# BMS_Carrier_-_AFE_Interface.net
KiCad netlist of a schematic drawn in Altium Designer
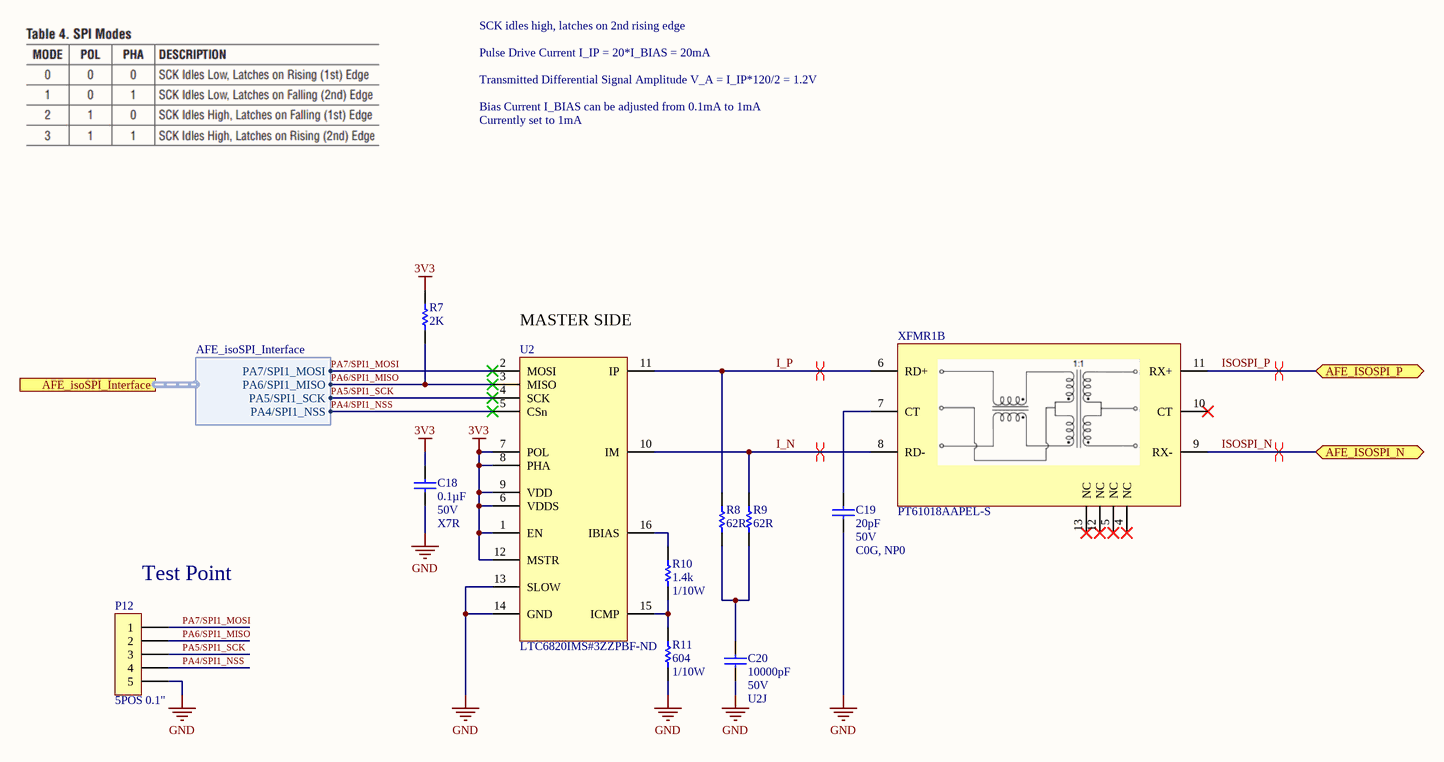
[diagram p0: BMS Carrier - AFE Interface.SchDoc]

(export (version "E")
  (design (tool "Eeschema 10.0.6"))
  (components
    (comp (ref "C18")
      (value "CAP CER 0.1UF 50V 10% X7R 0603")
      (footprint "CAP, 0603")
      (description "0.10µF ±10% 50V Ceramic Capacitor X7R 0603 (1608 Metric)")
      (fields
        (field (name "TOLERANCE") "±10%")
        (field (name "CAPACITANCE") "0.1µF")
        (field (name "VOLTAGE") "50V")
        (field (name "TEMPERATURE COEFFICIENT") "X7R")
      )
      (libsource (lib "Schematic Diagrams") (part "CAP CER 0.1UF 50V 10% X7R 0603"))
    )
    (comp (ref "C19")
      (value "CAP CER 20PF 50V ±5% C0G/NP0 0603")
      (footprint "CAP, 0603")
      (description "20pF ±5% 50V Ceramic Capacitor C0G, NP0 0603 (1608 Metric)")
      (fields
        (field (name "TOLERANCE") "±5%")
        (field (name "CAPACITANCE") "20pF")
        (field (name "VOLTAGE") "50V")
        (field (name "TEMPERATURE COEFFICIENT") "C0G, NP0")
      )
      (libsource (lib "Schematic Diagrams") (part "CAP CER 20PF 50V ±5% C0G/NP0 0603"))
    )
    (comp (ref "C20")
      (value "CAP CER 10nF 50V 5% X7R 0603")
      (footprint "CAP, 0603")
      (description "10000pF ±5% 50V Ceramic Capacitor U2J 0603 (1608 Metric)")
      (fields
        (field (name "TOLERANCE") "±5%")
        (field (name "CAPACITANCE") "10000pF")
        (field (name "VOLTAGE") "50V")
        (field (name "TEMPERATURE COEFFICIENT") "U2J")
      )
      (libsource (lib "Schematic Diagrams") (part "CAP CER 10nF 50V 5% X7R 0603"))
    )
    (comp (ref "P12")
      (value "5POS 0.1\"")
      (footprint "CONN, 5POS HEADR 0.1\"")
      (libsource (lib "Schematic Diagrams") (part "CONN 5POS HEADR MALE 0.1{dblquote}"))
    )
    (comp (ref "R7")
      (value "2K")
      (footprint "RES, 0603")
      (description "2k Ohm ±1% 0.1W, 1/10W Chip Resistor 0603 (1608 Metric) Moisture Resistant Thick Film")
      (fields
        (field (name "MANUFACTURER") "Yageo")
        (field (name "MANUFACTURER PART NUMBER") "RC0603FR-072KL")
      )
      (libsource (lib "Schematic Diagrams") (part "RES 2K OHM 1% 1/10W 0603"))
    )
    (comp (ref "R8")
      (value "62R")
      (footprint "RES, 0603")
      (description "62 Ohms ±0.1% 0.1W, 1/10W Chip Resistor 0603 (1608 Metric) Automotive AEC-Q200 Thin Film")
      (fields
        (field (name "MANUFACTURER") "Panasonic Electronic Components")
        (field (name "MANUFACTURER PART NUMBER") "ERA-3AEB620V")
      )
      (libsource (lib "Schematic Diagrams") (part "RES 62 OHM 0.1% 1/10W 0603"))
    )
    (comp (ref "R9")
      (value "62R")
      (footprint "RES, 0603")
      (description "62 Ohms ±0.1% 0.1W, 1/10W Chip Resistor 0603 (1608 Metric) Automotive AEC-Q200 Thin Film")
      (fields
        (field (name "MANUFACTURER") "Panasonic Electronic Components")
        (field (name "MANUFACTURER PART NUMBER") "ERA-3AEB620V")
      )
      (libsource (lib "Schematic Diagrams") (part "RES 62 OHM 0.1% 1/10W 0603"))
    )
    (comp (ref "R10")
      (value "RES 1.4k OHM 1% 1/10W 0603")
      (footprint "RES, 0603")
      (description "RES SMD 1.4K OHM 1% 1/10W 0603")
      (fields
        (field (name "TOLERANCE") "±1%")
        (field (name "RESISTANCE") "1.4k")
        (field (name "POWER") "1/10W")
      )
      (libsource (lib "Schematic Diagrams") (part "RES 1.4k OHM 1% 1/10W 0603"))
    )
    (comp (ref "R11")
      (value "RES 604 OHM 1% 1/10W 0603")
      (footprint "RES, 0603")
      (description "RES SMD 604 OHM 1% 1/10W 0603")
      (fields
        (field (name "TOLERANCE") "±1%")
        (field (name "RESISTANCE") "604")
        (field (name "POWER") "1/10W")
      )
      (libsource (lib "Schematic Diagrams") (part "RES 604 OHM 1% 1/10W 0603"))
    )
    (comp (ref "U2")
      (value "IC ISOSPI COMM INTERFACE LTC6820IMS#3ZZPBF")
      (footprint "IC isoSPI Interface LTC6820 MSOP")
      (description "IC COMM INTERFACE ISOSPI 16-MSOP")
      (fields
        (field (name "MANUFACTURER") "Linear Technology")
        (field (name "MANUFACTURER PART NUMBER") "LTC6820IMS#3ZZPBF")
        (field (name "SUPPLIER PART NUMBER 1") "LTC6820IMS#3ZZPBF-ND")
      )
      (libsource (lib "Schematic Diagrams") (part "IC ISOSPI COMM INTERFACE LTC6820IMS#3ZZPBF"))
    )
    (comp (ref "XFMR1")
      (value "IC PULSE XFMR 1CT:1CT 350UH SMD")
      (footprint "IC, PULSE XFMR 1CT:1CT 350UH SMD")
      (description "PULSE XFMR 1CT:1CT 350UH SMD")
      (fields (field (name "MANUFACTURER") "Bourns Inc.") (field (name "MFG_PN") "PT61018AAPEL-S"))
      (libsource (lib "Schematic Diagrams") (part "IC PULSE XFMR 1CT{colon}1CT 350UH SMD"))
    )
  )
  (nets
    (net (code "2") (name "/ISOSPI_N") (class "Default")
      (node (ref "XFMR1") (pin "9") (pinfunction "RX-_9") (pintype "passive"))
    )
    (net (code "3") (name "/ISOSPI_P") (class "Default")
      (node (ref "XFMR1") (pin "11") (pinfunction "RX+_11") (pintype "passive"))
    )
    (net (code "4") (name "/I_N") (class "Default")
      (node (ref "R9") (pin "1") (pinfunction "1_1") (pintype "passive"))
      (node (ref "U2") (pin "10") (pinfunction "IM_10") (pintype "passive"))
      (node (ref "XFMR1") (pin "8") (pinfunction "RD-_8") (pintype "passive"))
    )
    (net (code "5") (name "/I_P") (class "Default")
      (node (ref "R8") (pin "1") (pinfunction "1_1") (pintype "passive"))
      (node (ref "U2") (pin "11") (pinfunction "IP_11") (pintype "passive"))
      (node (ref "XFMR1") (pin "6") (pinfunction "RD+_6") (pintype "passive"))
    )
    (net (code "6") (name "/PA4{slash}SPI1_NSS") (class "Default")
      (node (ref "P12") (pin "4") (pinfunction "4_4") (pintype "passive"))
      (node (ref "U2") (pin "5") (pinfunction "CSn_5") (pintype "passive"))
    )
    (net (code "7") (name "/PA5{slash}SPI1_SCK") (class "Default")
      (node (ref "P12") (pin "3") (pinfunction "3_3") (pintype "passive"))
      (node (ref "U2") (pin "4") (pinfunction "SCK_4") (pintype "passive"))
    )
    (net (code "8") (name "/PA6{slash}SPI1_MISO") (class "Default")
      (node (ref "P12") (pin "2") (pinfunction "2_2") (pintype "passive"))
      (node (ref "R7") (pin "2") (pinfunction "2_2") (pintype "passive"))
      (node (ref "U2") (pin "3") (pinfunction "MISO_3") (pintype "passive"))
    )
    (net (code "9") (name "/PA7{slash}SPI1_MOSI") (class "Default")
      (node (ref "P12") (pin "1") (pinfunction "1_1") (pintype "passive"))
      (node (ref "U2") (pin "2") (pinfunction "MOSI_2") (pintype "passive"))
    )
    (net (code "11") (name "3V3") (class "Default")
      (node (ref "C18") (pin "1") (pinfunction "1_1") (pintype "passive"))
      (node (ref "R7") (pin "1") (pinfunction "1_1") (pintype "passive"))
      (node (ref "U2") (pin "1") (pinfunction "EN_1") (pintype "passive"))
      (node (ref "U2") (pin "12") (pinfunction "MSTR_12") (pintype "passive"))
      (node (ref "U2") (pin "6") (pinfunction "VDDS_6") (pintype "passive"))
      (node (ref "U2") (pin "7") (pinfunction "POL_7") (pintype "passive"))
      (node (ref "U2") (pin "8") (pinfunction "PHA_8") (pintype "passive"))
      (node (ref "U2") (pin "9") (pinfunction "VDD_9") (pintype "passive"))
    )
    (net (code "12") (name "GND") (class "Default")
      (node (ref "C18") (pin "2") (pinfunction "2_2") (pintype "passive"))
      (node (ref "C19") (pin "2") (pinfunction "2_2") (pintype "passive"))
      (node (ref "C20") (pin "2") (pinfunction "2_2") (pintype "passive"))
      (node (ref "P12") (pin "5") (pinfunction "5_5") (pintype "passive"))
      (node (ref "R11") (pin "2") (pinfunction "2_2") (pintype "passive"))
      (node (ref "U2") (pin "13") (pinfunction "SLOW_13") (pintype "passive"))
      (node (ref "U2") (pin "14") (pinfunction "GND_14") (pintype "passive"))
    )
    (net (code "13") (name "Net-(C19-Pad1)") (class "Default")
      (node (ref "C19") (pin "1") (pinfunction "1_1") (pintype "passive"))
      (node (ref "XFMR1") (pin "7") (pinfunction "CT_7") (pintype "passive"))
    )
    (net (code "14") (name "Net-(C20-Pad1)") (class "Default")
      (node (ref "C20") (pin "1") (pinfunction "1_1") (pintype "passive"))
      (node (ref "R8") (pin "2") (pinfunction "2_2") (pintype "passive"))
      (node (ref "R9") (pin "2") (pinfunction "2_2") (pintype "passive"))
    )
    (net (code "15") (name "Net-(U2-IBIAS)") (class "Default")
      (node (ref "R10") (pin "1") (pinfunction "1_1") (pintype "passive"))
      (node (ref "U2") (pin "16") (pinfunction "IBIAS_16") (pintype "passive"))
    )
    (net (code "16") (name "Net-(U2-ICMP)") (class "Default")
      (node (ref "R10") (pin "2") (pinfunction "2_2") (pintype "passive"))
      (node (ref "R11") (pin "1") (pinfunction "1_1") (pintype "passive"))
      (node (ref "U2") (pin "15") (pinfunction "ICMP_15") (pintype "passive"))
    )
    (net (code "17") (name "unconnected-(XFMR1B-CT-Pad10)") (class "Default")
      (node (ref "XFMR1") (pin "10") (pinfunction "CT_10") (pintype "passive+no_connect"))
    )
    (net (code "18") (name "unconnected-(XFMR1B-NC-Pad4)") (class "Default")
      (node (ref "XFMR1") (pin "4") (pinfunction "NC_4") (pintype "passive+no_connect"))
    )
    (net (code "19") (name "unconnected-(XFMR1B-NC-Pad5)") (class "Default")
      (node (ref "XFMR1") (pin "5") (pinfunction "NC_5") (pintype "passive+no_connect"))
    )
    (net (code "20") (name "unconnected-(XFMR1B-NC-Pad12)") (class "Default")
      (node (ref "XFMR1") (pin "12") (pinfunction "NC_12") (pintype "passive+no_connect"))
    )
    (net (code "21") (name "unconnected-(XFMR1B-NC-Pad13)") (class "Default")
      (node (ref "XFMR1") (pin "13") (pinfunction "NC_13") (pintype "passive+no_connect"))
    )
  )
)
